# LED-Board.net
KiCad netlist of a schematic drawn in EAGLE
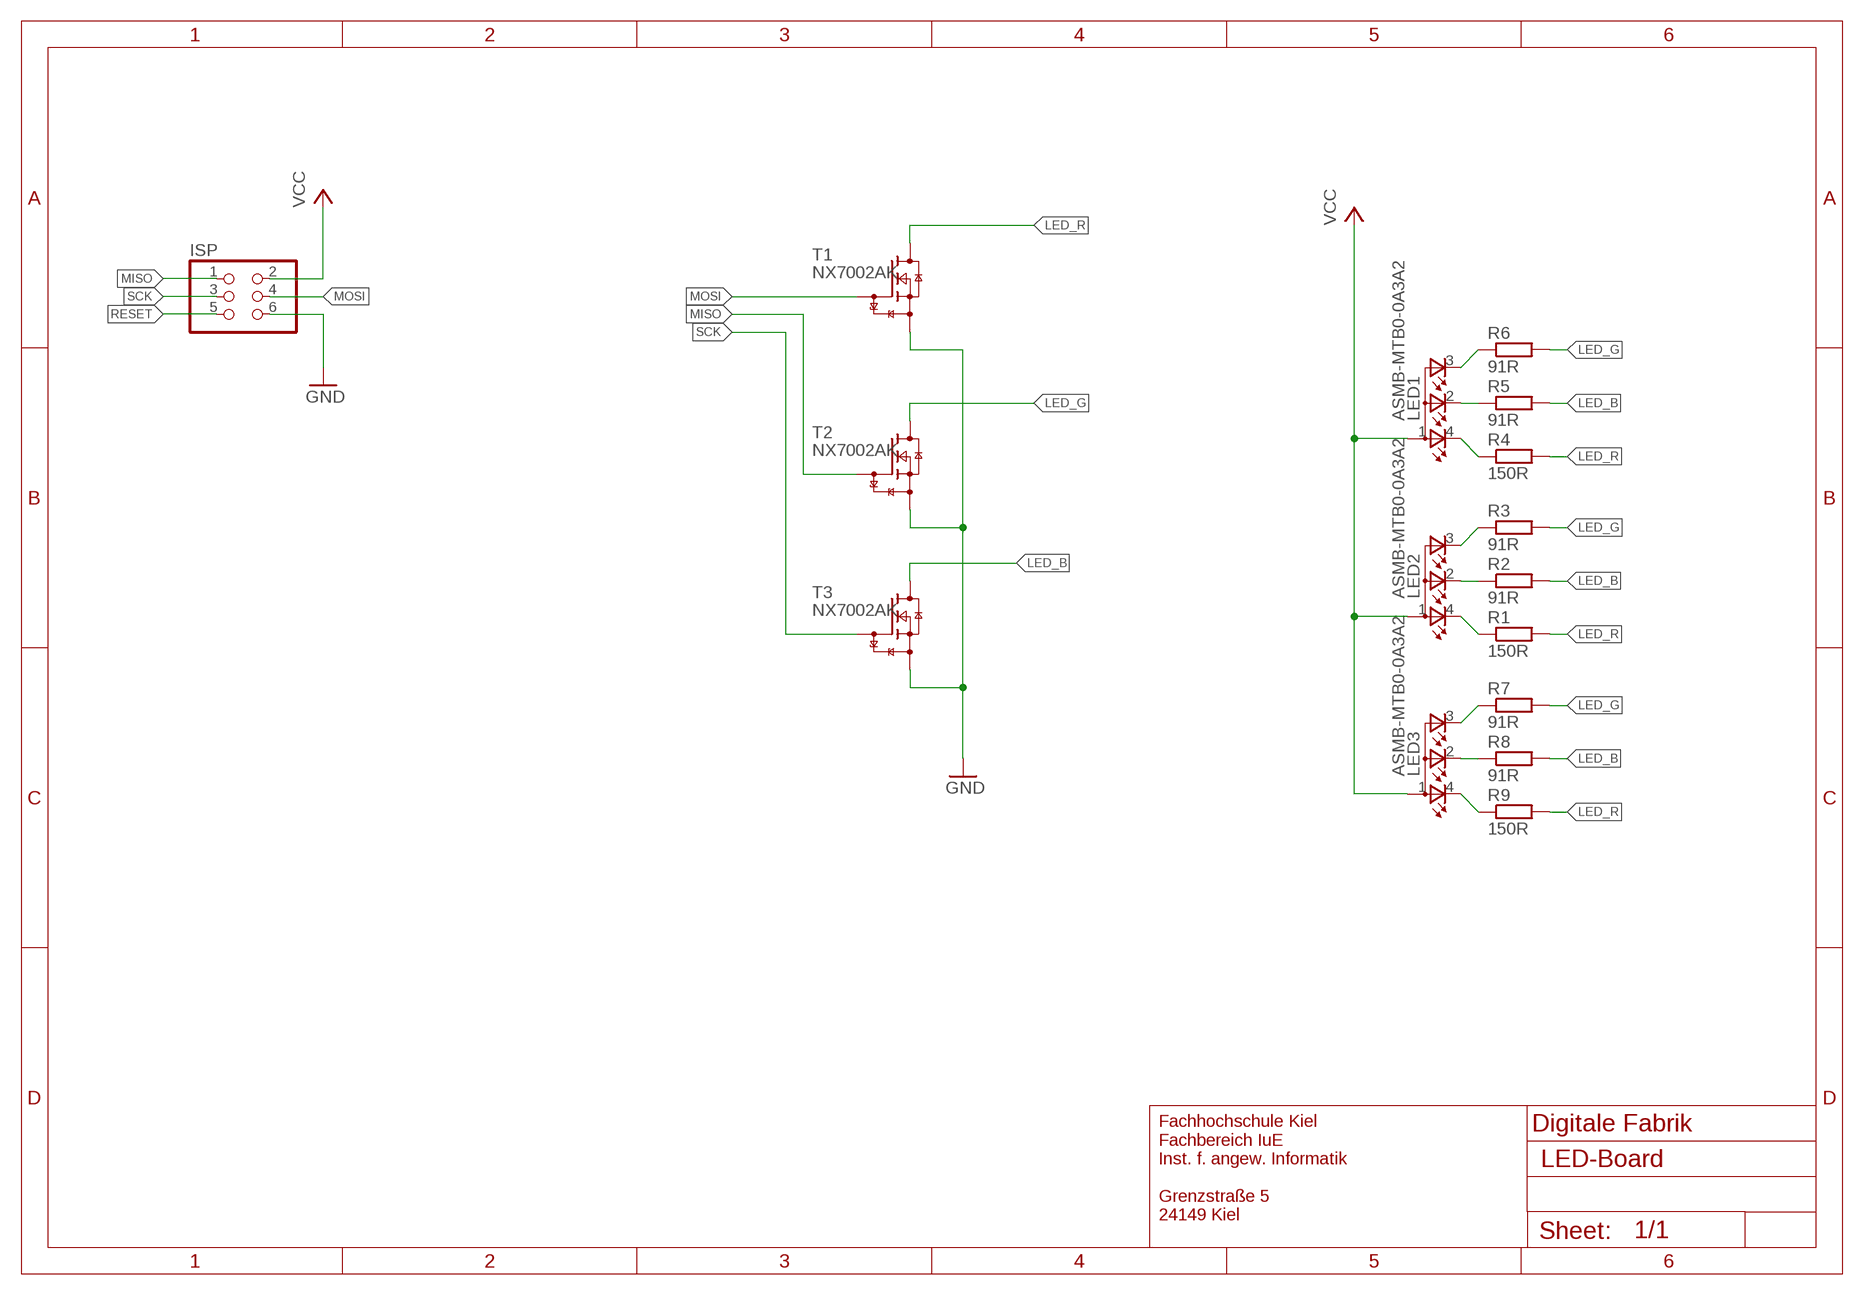
[diagram p0: schematic, sheet 1]

(export (version "E")
  (design (tool "Eeschema 10.0.6"))
  (components
    (comp (ref "ISP")
      (value "PINHD-2X03_2.54-SMD")
      (footprint "eagle-import:2X03SMD")
      (libsource (lib "eagle-import") (part "PINHD-2X03_2.54-SMD"))
    )
    (comp (ref "LED1")
      (value "ASMB-MTB0-0A3A2")
      (footprint "eagle-import:P-LCC-4-3")
      (libsource (lib "eagle-import") (part "PLCC4"))
    )
    (comp (ref "LED2")
      (value "ASMB-MTB0-0A3A2")
      (footprint "eagle-import:P-LCC-4-3")
      (libsource (lib "eagle-import") (part "PLCC4"))
    )
    (comp (ref "LED3")
      (value "ASMB-MTB0-0A3A2")
      (footprint "eagle-import:P-LCC-4-3")
      (libsource (lib "eagle-import") (part "PLCC4"))
    )
    (comp (ref "R1")
      (value "150R")
      (footprint "eagle-import:R0805")
      (libsource (lib "eagle-import") (part "R-EU_R0805"))
    )
    (comp (ref "R2")
      (value "91R")
      (footprint "eagle-import:R0805")
      (libsource (lib "eagle-import") (part "R-EU_R0805"))
    )
    (comp (ref "R3")
      (value "91R")
      (footprint "eagle-import:R0805")
      (libsource (lib "eagle-import") (part "R-EU_R0805"))
    )
    (comp (ref "R4")
      (value "150R")
      (footprint "eagle-import:R0805")
      (libsource (lib "eagle-import") (part "R-EU_R0805"))
    )
    (comp (ref "R5")
      (value "91R")
      (footprint "eagle-import:R0805")
      (libsource (lib "eagle-import") (part "R-EU_R0805"))
    )
    (comp (ref "R6")
      (value "91R")
      (footprint "eagle-import:R0805")
      (libsource (lib "eagle-import") (part "R-EU_R0805"))
    )
    (comp (ref "R7")
      (value "91R")
      (footprint "eagle-import:R0805")
      (libsource (lib "eagle-import") (part "R-EU_R0805"))
    )
    (comp (ref "R8")
      (value "91R")
      (footprint "eagle-import:R0805")
      (libsource (lib "eagle-import") (part "R-EU_R0805"))
    )
    (comp (ref "R9")
      (value "150R")
      (footprint "eagle-import:R0805")
      (libsource (lib "eagle-import") (part "R-EU_R0805"))
    )
    (comp (ref "T1")
      (value "NX7002AK")
      (footprint "eagle-import:SOT23")
      (libsource (lib "eagle-import") (part "2N7002CK"))
    )
    (comp (ref "T2")
      (value "NX7002AK")
      (footprint "eagle-import:SOT23")
      (libsource (lib "eagle-import") (part "2N7002CK"))
    )
    (comp (ref "T3")
      (value "NX7002AK")
      (footprint "eagle-import:SOT23")
      (libsource (lib "eagle-import") (part "2N7002CK"))
    )
  )
  (nets
    (net (code "1") (name "GND") (class "Default")
      (node (ref "ISP") (pin "6") (pinfunction "6_6") (pintype "passive"))
      (node (ref "T1") (pin "2") (pinfunction "S_2") (pintype "passive"))
      (node (ref "T2") (pin "2") (pinfunction "S_2") (pintype "passive"))
      (node (ref "T3") (pin "2") (pinfunction "S_2") (pintype "passive"))
    )
    (net (code "2") (name "LED_B") (class "Default")
      (node (ref "R2") (pin "2") (pinfunction "2_2") (pintype "passive"))
      (node (ref "R5") (pin "2") (pinfunction "2_2") (pintype "passive"))
      (node (ref "R8") (pin "2") (pinfunction "2_2") (pintype "passive"))
      (node (ref "T3") (pin "3") (pinfunction "D_3") (pintype "passive"))
    )
    (net (code "3") (name "LED_G") (class "Default")
      (node (ref "R3") (pin "2") (pinfunction "2_2") (pintype "passive"))
      (node (ref "R6") (pin "2") (pinfunction "2_2") (pintype "passive"))
      (node (ref "R7") (pin "2") (pinfunction "2_2") (pintype "passive"))
      (node (ref "T2") (pin "3") (pinfunction "D_3") (pintype "passive"))
    )
    (net (code "4") (name "LED_R") (class "Default")
      (node (ref "R1") (pin "2") (pinfunction "2_2") (pintype "passive"))
      (node (ref "R4") (pin "2") (pinfunction "2_2") (pintype "passive"))
      (node (ref "R9") (pin "2") (pinfunction "2_2") (pintype "passive"))
      (node (ref "T1") (pin "3") (pinfunction "D_3") (pintype "passive"))
    )
    (net (code "5") (name "MISO") (class "Default")
      (node (ref "ISP") (pin "1") (pinfunction "1_1") (pintype "passive"))
      (node (ref "T2") (pin "1") (pinfunction "G_1") (pintype "passive"))
    )
    (net (code "6") (name "MOSI") (class "Default")
      (node (ref "ISP") (pin "4") (pinfunction "4_4") (pintype "passive"))
      (node (ref "T1") (pin "1") (pinfunction "G_1") (pintype "passive"))
    )
    (net (code "7") (name "Net-(LED1-CBLUE)") (class "Default")
      (node (ref "LED1") (pin "2") (pinfunction "CBLUE_2") (pintype "passive"))
      (node (ref "R5") (pin "1") (pinfunction "1_1") (pintype "passive"))
    )
    (net (code "8") (name "Net-(LED1-CGREEN)") (class "Default")
      (node (ref "LED1") (pin "3") (pinfunction "CGREEN_3") (pintype "passive"))
      (node (ref "R6") (pin "1") (pinfunction "1_1") (pintype "passive"))
    )
    (net (code "9") (name "Net-(LED1-CRED)") (class "Default")
      (node (ref "LED1") (pin "4") (pinfunction "CRED_4") (pintype "passive"))
      (node (ref "R4") (pin "1") (pinfunction "1_1") (pintype "passive"))
    )
    (net (code "10") (name "Net-(LED2-CBLUE)") (class "Default")
      (node (ref "LED2") (pin "2") (pinfunction "CBLUE_2") (pintype "passive"))
      (node (ref "R2") (pin "1") (pinfunction "1_1") (pintype "passive"))
    )
    (net (code "11") (name "Net-(LED2-CGREEN)") (class "Default")
      (node (ref "LED2") (pin "3") (pinfunction "CGREEN_3") (pintype "passive"))
      (node (ref "R3") (pin "1") (pinfunction "1_1") (pintype "passive"))
    )
    (net (code "12") (name "Net-(LED2-CRED)") (class "Default")
      (node (ref "LED2") (pin "4") (pinfunction "CRED_4") (pintype "passive"))
      (node (ref "R1") (pin "1") (pinfunction "1_1") (pintype "passive"))
    )
    (net (code "13") (name "Net-(LED3-CBLUE)") (class "Default")
      (node (ref "LED3") (pin "2") (pinfunction "CBLUE_2") (pintype "passive"))
      (node (ref "R8") (pin "1") (pinfunction "1_1") (pintype "passive"))
    )
    (net (code "14") (name "Net-(LED3-CGREEN)") (class "Default")
      (node (ref "LED3") (pin "3") (pinfunction "CGREEN_3") (pintype "passive"))
      (node (ref "R7") (pin "1") (pinfunction "1_1") (pintype "passive"))
    )
    (net (code "15") (name "Net-(LED3-CRED)") (class "Default")
      (node (ref "LED3") (pin "4") (pinfunction "CRED_4") (pintype "passive"))
      (node (ref "R9") (pin "1") (pinfunction "1_1") (pintype "passive"))
    )
    (net (code "16") (name "RESET") (class "Default")
      (node (ref "ISP") (pin "5") (pinfunction "5_5") (pintype "passive"))
    )
    (net (code "17") (name "SCK") (class "Default")
      (node (ref "ISP") (pin "3") (pinfunction "3_3") (pintype "passive"))
      (node (ref "T3") (pin "1") (pinfunction "G_1") (pintype "passive"))
    )
    (net (code "18") (name "VCC") (class "Default")
      (node (ref "ISP") (pin "2") (pinfunction "2_2") (pintype "passive"))
      (node (ref "LED1") (pin "1") (pinfunction "A2_1") (pintype "passive"))
      (node (ref "LED2") (pin "1") (pinfunction "A2_1") (pintype "passive"))
      (node (ref "LED3") (pin "1") (pinfunction "A2_1") (pintype "passive"))
    )
  )
)
